# PA_stage_1.net
KiCad netlist of a schematic drawn in Altium Designer
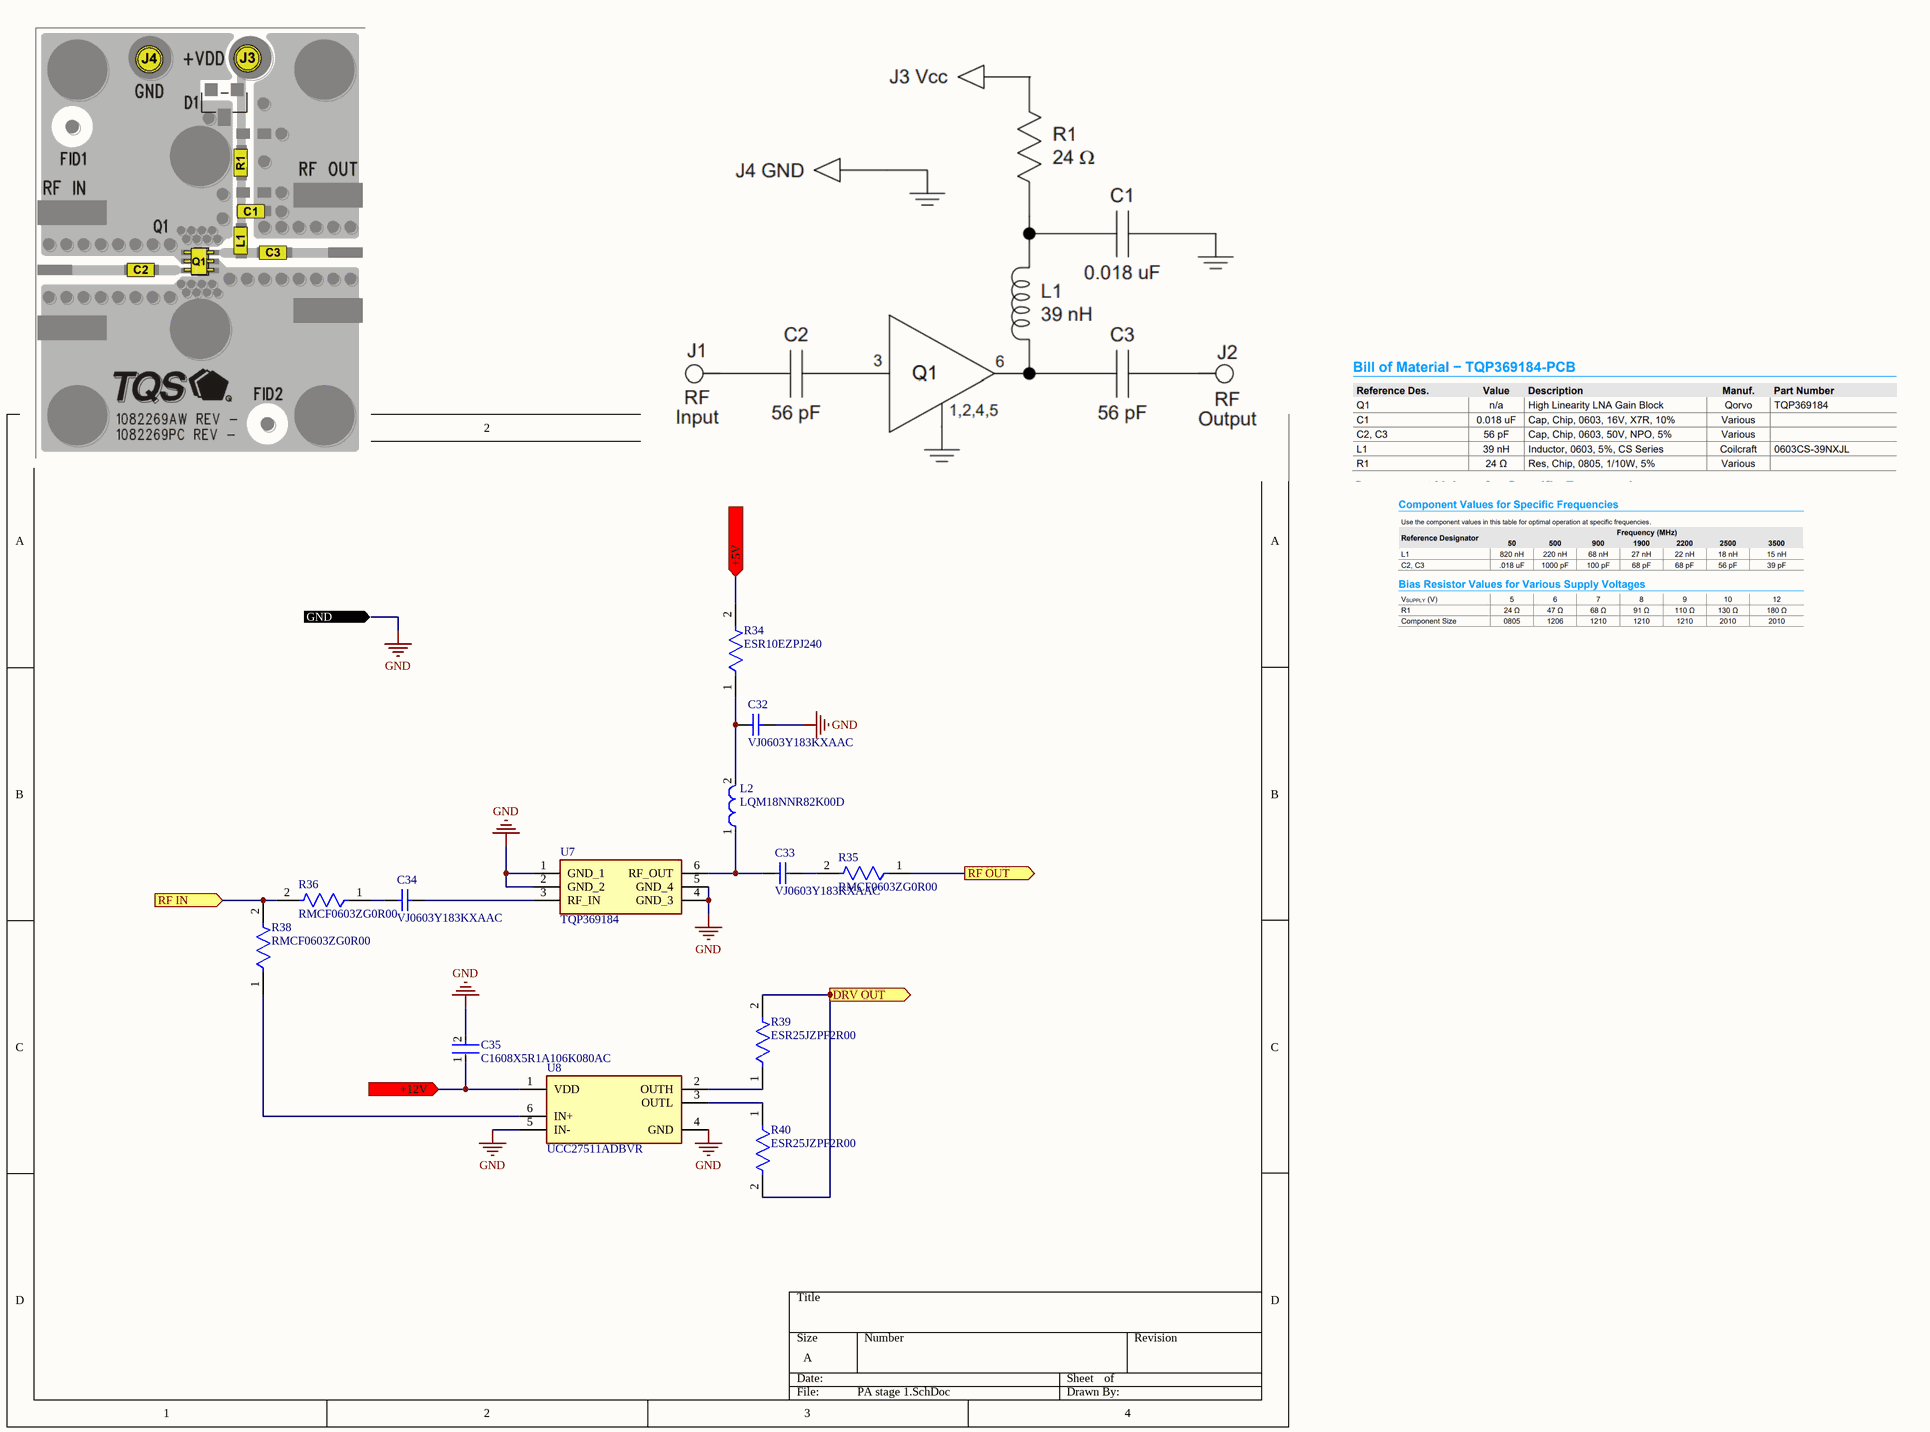
[diagram p0: PA stage 1.SchDoc]

(export (version "E")
  (design (tool "Eeschema 10.0.6"))
  (components
    (comp (ref "C32")
      (value "VJ0603Y183KXAAC")
      (footprint "CAPC1608X92X38ML15T08")
      (fields (field (name "MANUFACTURER") "Vitramon"))
      (libsource (lib "Altium Content Vault") (part "CAP"))
    )
    (comp (ref "C33")
      (value "VJ0603Y183KXAAC")
      (footprint "CAPC1608X92X38ML15T08")
      (fields (field (name "MANUFACTURER") "Vitramon"))
      (libsource (lib "Altium Content Vault") (part "CAP"))
    )
    (comp (ref "C34")
      (value "VJ0603Y183KXAAC")
      (footprint "CAPC1608X92X38ML15T08")
      (fields (field (name "MANUFACTURER") "Vitramon"))
      (libsource (lib "Altium Content Vault") (part "CAP"))
    )
    (comp (ref "C35")
      (value "C1608X5R1A106K080AC")
      (footprint "FP-C1608-080-0_1-MFG")
      (description "Multilayer Ceramic Capacitors 10μF ±10% 10V X5R SMD 0603")
      (fields (field (name "VOLTAGE") "10V") (field (name "TOLERANCE") "10%"))
      (libsource (lib "Altium Content Vault") (part "236180d848d6139a670b325ea6854c9"))
    )
    (comp (ref "L2")
      (value "LQM18NNR82K00D")
      (footprint "FP-LQM18NN_00-IPC_B")
      (description "Multilayer Type Inductor for General Circuits, 0603 (1608), 820nH, 10%, 2.1Ω, 35mA")
      (fields (field (name "TOLERANCE") "10%"))
      (libsource (lib "Altium Content Vault") (part "725321dda6339637d4d059423bc1c3c"))
    )
    (comp (ref "R34")
      (value "ESR10EZPJ240")
      (footprint "FP-ESR10-IPC_C")
      (description "24Ω ±5% 0.4W 0805 Anti-Surge Chip Resistor AEC-Q200")
      (fields (field (name "TOLERANCE") "5%"))
      (libsource (lib "Altium Content Vault") (part "1029c3af85768c4190bb7ad29bc67b5"))
    )
    (comp (ref "R35")
      (value "RMCF0603ZG0R00")
      (footprint "FP-RMCF0603-IPC_B")
      (description "0Ω ±0 0.1W 0603 Thick Film Chip Resistor AEC-Q200 compliant")
      (libsource (lib "Altium Content Vault") (part "1029c3af85768c4190bb7ad29bc67b5"))
    )
    (comp (ref "R36")
      (value "RMCF0603ZG0R00")
      (footprint "FP-RMCF0603-IPC_B")
      (description "0Ω ±0 0.1W 0603 Thick Film Chip Resistor AEC-Q200 compliant")
      (libsource (lib "Altium Content Vault") (part "1029c3af85768c4190bb7ad29bc67b5"))
    )
    (comp (ref "R38")
      (value "RMCF0603ZG0R00")
      (footprint "FP-RMCF0603-IPC_B")
      (description "0Ω ±0 0.1W 0603 Thick Film Chip Resistor AEC-Q200 compliant")
      (libsource (lib "Altium Content Vault") (part "1029c3af85768c4190bb7ad29bc67b5"))
    )
    (comp (ref "R39")
      (value "ESR25JZPF2R00")
      (footprint "FP-ESR25-MFG")
      (description "2Ω ±1% 0.66W 1210 Anti-Surge Chip Resistor AEC-Q200")
      (fields (field (name "TOLERANCE") "1%"))
      (libsource (lib "Altium Content Vault") (part "1029c3af85768c4190bb7ad29bc67b5"))
    )
    (comp (ref "R40")
      (value "ESR25JZPF2R00")
      (footprint "FP-ESR25-MFG")
      (description "2Ω ±1% 0.66W 1210 Anti-Surge Chip Resistor AEC-Q200")
      (fields (field (name "TOLERANCE") "1%"))
      (libsource (lib "Altium Content Vault") (part "1029c3af85768c4190bb7ad29bc67b5"))
    )
    (comp (ref "U7")
      (value "TQP369184")
      (footprint "SOT65P210X110-6N")
      (description "DC  6 GHz Gain Block")
      (fields (field (name "MOUSER PART NUMBER") "772-TQP369184"))
      (libsource (lib "TQP369184") (part "TQP369184"))
    )
    (comp (ref "U8")
      (value "UCC27511ADBVR")
      (footprint "FP-DBV0006A-IPC_B")
      (description "IC GATE DRVR LOW-SIDE SOT23-6")
      (libsource (lib "Altium Content Vault") (part "9cea8d48b3c5e665674ac7ab8f980b4"))
    )
  )
  (nets
    (net (code "1") (name "/+5V") (class "Default")
      (node (ref "R34") (pin "2") (pinfunction "2_2") (pintype "passive"))
    )
    (net (code "2") (name "/+12V") (class "Default")
      (node (ref "C35") (pin "1") (pinfunction "1_1") (pintype "passive"))
      (node (ref "U8") (pin "1") (pinfunction "VDD_1") (pintype "power_in"))
    )
    (net (code "3") (name "/DRV OUT") (class "Default")
      (node (ref "R39") (pin "2") (pinfunction "2_2") (pintype "passive"))
      (node (ref "R40") (pin "2") (pinfunction "2_2") (pintype "passive"))
    )
    (net (code "4") (name "/RF IN") (class "Default")
      (node (ref "R36") (pin "2") (pinfunction "2_2") (pintype "passive"))
      (node (ref "R38") (pin "2") (pinfunction "2_2") (pintype "passive"))
    )
    (net (code "5") (name "/RF OUT") (class "Default")
      (node (ref "R35") (pin "1") (pinfunction "1_1") (pintype "passive"))
    )
    (net (code "6") (name "GND") (class "Default")
      (node (ref "C32") (pin "2") (pinfunction "2_2") (pintype "passive"))
      (node (ref "C35") (pin "2") (pinfunction "2_2") (pintype "passive"))
      (node (ref "U7") (pin "1") (pinfunction "GND_1_1") (pintype "passive"))
      (node (ref "U7") (pin "2") (pinfunction "GND_2_2") (pintype "passive"))
      (node (ref "U7") (pin "4") (pinfunction "GND_3_4") (pintype "passive"))
      (node (ref "U7") (pin "5") (pinfunction "GND_4_5") (pintype "passive"))
      (node (ref "U8") (pin "4") (pinfunction "GND_4") (pintype "power_in"))
      (node (ref "U8") (pin "5") (pinfunction "IN-_5") (pintype "tri_state"))
    )
    (net (code "7") (name "Net-(C32-Pad1)") (class "Default")
      (node (ref "C32") (pin "1") (pinfunction "1_1") (pintype "passive"))
      (node (ref "L2") (pin "2") (pinfunction "2_2") (pintype "passive"))
      (node (ref "R34") (pin "1") (pinfunction "1_1") (pintype "passive"))
    )
    (net (code "8") (name "Net-(C33-Pad2)") (class "Default")
      (node (ref "C33") (pin "2") (pinfunction "2_2") (pintype "passive"))
      (node (ref "R35") (pin "2") (pinfunction "2_2") (pintype "passive"))
    )
    (net (code "9") (name "Net-(C34-Pad1)") (class "Default")
      (node (ref "C34") (pin "1") (pinfunction "1_1") (pintype "passive"))
      (node (ref "R36") (pin "1") (pinfunction "1_1") (pintype "passive"))
    )
    (net (code "10") (name "Net-(U7-RF_IN)") (class "Default")
      (node (ref "C34") (pin "2") (pinfunction "2_2") (pintype "passive"))
      (node (ref "U7") (pin "3") (pinfunction "RF_IN_3") (pintype "passive"))
    )
    (net (code "11") (name "Net-(U7-RF_OUT)") (class "Default")
      (node (ref "C33") (pin "1") (pinfunction "1_1") (pintype "passive"))
      (node (ref "L2") (pin "1") (pinfunction "1_1") (pintype "passive"))
      (node (ref "U7") (pin "6") (pinfunction "RF_OUT_6") (pintype "passive"))
    )
    (net (code "12") (name "Net-(U8-IN+)") (class "Default")
      (node (ref "R38") (pin "1") (pinfunction "1_1") (pintype "passive"))
      (node (ref "U8") (pin "6") (pinfunction "IN+_6") (pintype "tri_state"))
    )
    (net (code "13") (name "Net-(U8-OUTH)") (class "Default")
      (node (ref "R39") (pin "1") (pinfunction "1_1") (pintype "passive"))
      (node (ref "U8") (pin "2") (pinfunction "OUTH_2") (pintype "passive"))
    )
    (net (code "14") (name "Net-(U8-OUTL)") (class "Default")
      (node (ref "R40") (pin "1") (pinfunction "1_1") (pintype "passive"))
      (node (ref "U8") (pin "3") (pinfunction "OUTL_3") (pintype "passive"))
    )
  )
)
